# Christmas_Tree_2_1.net
KiCad netlist of a schematic drawn in EAGLE
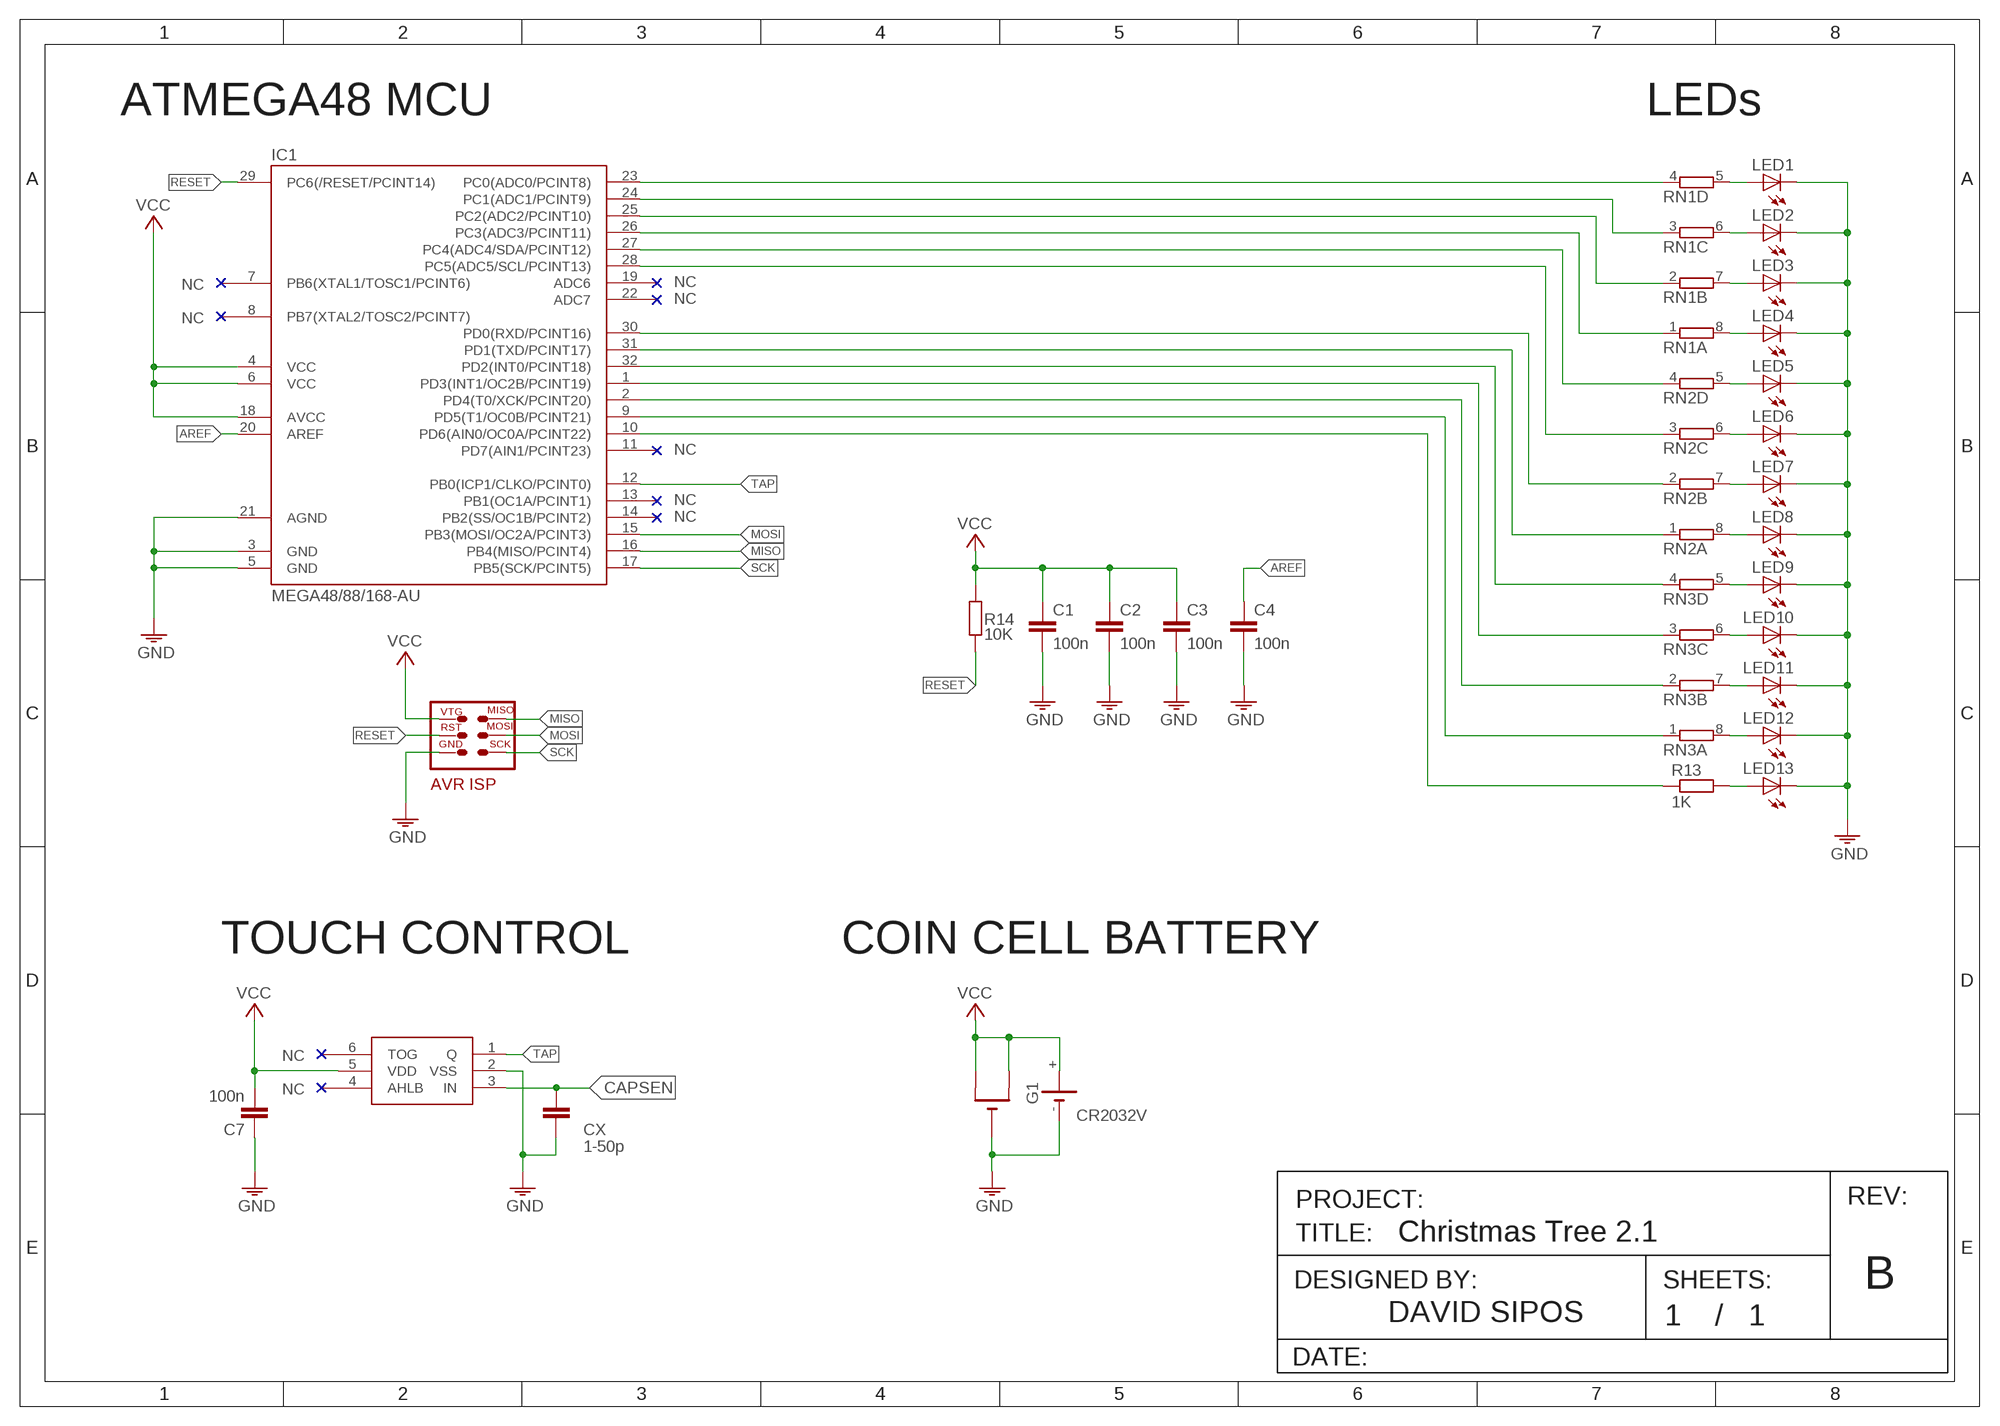
[diagram p0: schematic, sheet 1]

(export (version "E")
  (design (tool "Eeschema 10.0.6"))
  (components
    (comp (ref "BAT")
      (value "CR2032SMT")
      (footprint "eagle-import:CR2032-SMD")
      (libsource (lib "eagle-import") (part "CR2032SMT"))
    )
    (comp (ref "C1")
      (value "100n")
      (footprint "eagle-import:C0402K")
      (libsource (lib "eagle-import") (part "C-EUC0402K"))
    )
    (comp (ref "C2")
      (value "100n")
      (footprint "eagle-import:C0402K")
      (libsource (lib "eagle-import") (part "C-EUC0402K"))
    )
    (comp (ref "C3")
      (value "100n")
      (footprint "eagle-import:C0402K")
      (libsource (lib "eagle-import") (part "C-EUC0402K"))
    )
    (comp (ref "C4")
      (value "100n")
      (footprint "eagle-import:C0402K")
      (libsource (lib "eagle-import") (part "C-EUC0402K"))
    )
    (comp (ref "C7")
      (value "100n")
      (footprint "eagle-import:C0402K")
      (libsource (lib "eagle-import") (part "C-EUC0402K"))
    )
    (comp (ref "CX")
      (value "1-50p")
      (footprint "eagle-import:C0402K")
      (libsource (lib "eagle-import") (part "C-EUC0402K"))
    )
    (comp (ref "G1")
      (value "CR2032V")
      (footprint "eagle-import:CR2032V")
      (libsource (lib "eagle-import") (part "CR2032V"))
    )
    (comp (ref "IC1")
      (value "MEGA48/88/168-AU")
      (footprint "eagle-import:TQFP32-08")
      (libsource (lib "eagle-import") (part "MEGA48/88/168-AU"))
    )
    (comp (ref "LED1")
      (value "LEDCHIPLED_0805")
      (footprint "eagle-import:CHIPLED_0805")
      (libsource (lib "eagle-import") (part "LEDCHIPLED_0805"))
    )
    (comp (ref "LED2")
      (value "LEDCHIPLED_0805")
      (footprint "eagle-import:CHIPLED_0805")
      (libsource (lib "eagle-import") (part "LEDCHIPLED_0805"))
    )
    (comp (ref "LED3")
      (value "LEDCHIPLED_0805")
      (footprint "eagle-import:CHIPLED_0805")
      (libsource (lib "eagle-import") (part "LEDCHIPLED_0805"))
    )
    (comp (ref "LED4")
      (value "LEDCHIPLED_0805")
      (footprint "eagle-import:CHIPLED_0805")
      (libsource (lib "eagle-import") (part "LEDCHIPLED_0805"))
    )
    (comp (ref "LED5")
      (value "LEDCHIPLED_0805")
      (footprint "eagle-import:CHIPLED_0805")
      (libsource (lib "eagle-import") (part "LEDCHIPLED_0805"))
    )
    (comp (ref "LED6")
      (value "LEDCHIPLED_0805")
      (footprint "eagle-import:CHIPLED_0805")
      (libsource (lib "eagle-import") (part "LEDCHIPLED_0805"))
    )
    (comp (ref "LED7")
      (value "LEDCHIPLED_0805")
      (footprint "eagle-import:CHIPLED_0805")
      (libsource (lib "eagle-import") (part "LEDCHIPLED_0805"))
    )
    (comp (ref "LED8")
      (value "LEDCHIPLED_0805")
      (footprint "eagle-import:CHIPLED_0805")
      (libsource (lib "eagle-import") (part "LEDCHIPLED_0805"))
    )
    (comp (ref "LED9")
      (value "LEDCHIPLED_0805")
      (footprint "eagle-import:CHIPLED_0805")
      (libsource (lib "eagle-import") (part "LEDCHIPLED_0805"))
    )
    (comp (ref "LED10")
      (value "LEDCHIPLED_0805")
      (footprint "eagle-import:CHIPLED_0805")
      (libsource (lib "eagle-import") (part "LEDCHIPLED_0805"))
    )
    (comp (ref "LED11")
      (value "LEDCHIPLED_0805")
      (footprint "eagle-import:CHIPLED_0805")
      (libsource (lib "eagle-import") (part "LEDCHIPLED_0805"))
    )
    (comp (ref "LED12")
      (value "LEDCHIPLED_0805")
      (footprint "eagle-import:CHIPLED_0805")
      (libsource (lib "eagle-import") (part "LEDCHIPLED_0805"))
    )
    (comp (ref "LED13")
      (value "LEDCHIPLED_0805")
      (footprint "eagle-import:CHIPLED_0805")
      (libsource (lib "eagle-import") (part "LEDCHIPLED_0805"))
    )
    (comp (ref "R13")
      (value "1K")
      (footprint "eagle-import:R0402")
      (libsource (lib "eagle-import") (part "R-EU_R0402"))
    )
    (comp (ref "R14")
      (value "10K")
      (footprint "eagle-import:R0402")
      (libsource (lib "eagle-import") (part "R-EU_R0402"))
    )
    (comp (ref "RN1")
      (value "4R-N0603-ARC")
      (footprint "eagle-import:0603-ARC")
      (libsource (lib "eagle-import") (part "4R-N0603-ARC"))
    )
    (comp (ref "RN2")
      (value "4R-N0603-ARC")
      (footprint "eagle-import:0603-ARC")
      (libsource (lib "eagle-import") (part "4R-N0603-ARC"))
    )
    (comp (ref "RN3")
      (value "4R-N0603-ARC")
      (footprint "eagle-import:0603-ARC")
      (libsource (lib "eagle-import") (part "4R-N0603-ARC"))
    )
    (comp (ref "TTP223E1")
      (value "TTP223E")
      (footprint "eagle-import:SOT23-6")
      (libsource (lib "eagle-import") (part "TTP223E"))
    )
    (comp (ref "U$12")
      (value "ISP")
      (footprint "eagle-import:ISP")
      (libsource (lib "eagle-import") (part "ISP"))
    )
  )
  (nets
    (net (code "1") (name "AREF") (class "Default")
      (node (ref "C4") (pin "1") (pinfunction "1_1") (pintype "passive"))
      (node (ref "IC1") (pin "20") (pinfunction "AREF_20") (pintype "passive"))
    )
    (net (code "2") (name "CAPSEN") (class "Default")
      (node (ref "CX") (pin "2") (pinfunction "2_2") (pintype "passive"))
      (node (ref "TTP223E1") (pin "3") (pinfunction "IN_3") (pintype "bidirectional"))
    )
    (net (code "3") (name "GND") (class "Default")
      (node (ref "BAT") (pin "-") (pinfunction "-_-") (pintype "passive"))
      (node (ref "C1") (pin "2") (pinfunction "2_2") (pintype "passive"))
      (node (ref "C2") (pin "2") (pinfunction "2_2") (pintype "passive"))
      (node (ref "C3") (pin "2") (pinfunction "2_2") (pintype "passive"))
      (node (ref "C4") (pin "2") (pinfunction "2_2") (pintype "passive"))
      (node (ref "C7") (pin "1") (pinfunction "1_1") (pintype "passive"))
      (node (ref "CX") (pin "1") (pinfunction "1_1") (pintype "passive"))
      (node (ref "G1") (pin "-") (pinfunction "-_-") (pintype "passive"))
      (node (ref "IC1") (pin "21") (pinfunction "AGND_21") (pintype "power_in"))
      (node (ref "IC1") (pin "3") (pinfunction "GND_3") (pintype "power_in"))
      (node (ref "IC1") (pin "5") (pinfunction "GND_5") (pintype "power_in"))
      (node (ref "LED1") (pin "C") (pinfunction "C_C") (pintype "passive"))
      (node (ref "LED10") (pin "C") (pinfunction "C_C") (pintype "passive"))
      (node (ref "LED11") (pin "C") (pinfunction "C_C") (pintype "passive"))
      (node (ref "LED12") (pin "C") (pinfunction "C_C") (pintype "passive"))
      (node (ref "LED13") (pin "C") (pinfunction "C_C") (pintype "passive"))
      (node (ref "LED2") (pin "C") (pinfunction "C_C") (pintype "passive"))
      (node (ref "LED3") (pin "C") (pinfunction "C_C") (pintype "passive"))
      (node (ref "LED4") (pin "C") (pinfunction "C_C") (pintype "passive"))
      (node (ref "LED5") (pin "C") (pinfunction "C_C") (pintype "passive"))
      (node (ref "LED6") (pin "C") (pinfunction "C_C") (pintype "passive"))
      (node (ref "LED7") (pin "C") (pinfunction "C_C") (pintype "passive"))
      (node (ref "LED8") (pin "C") (pinfunction "C_C") (pintype "passive"))
      (node (ref "LED9") (pin "C") (pinfunction "C_C") (pintype "passive"))
      (node (ref "TTP223E1") (pin "2") (pinfunction "VSS_2") (pintype "bidirectional"))
      (node (ref "U$12") (pin "6") (pinfunction "6_6") (pintype "passive"))
    )
    (net (code "4") (name "MISO") (class "Default")
      (node (ref "IC1") (pin "16") (pinfunction "PB4(MISO/PCINT4)_16") (pintype "bidirectional"))
      (node (ref "U$12") (pin "1") (pinfunction "1_1") (pintype "passive"))
    )
    (net (code "5") (name "MOSI") (class "Default")
      (node (ref "IC1") (pin "15") (pinfunction "PB3(MOSI/OC2A/PCINT3)_15") (pintype "bidirectional"))
      (node (ref "U$12") (pin "4") (pinfunction "4_4") (pintype "passive"))
    )
    (net (code "6") (name "Net-(IC1-PC0(ADC0{slash}PCINT8))") (class "Default")
      (node (ref "IC1") (pin "23") (pinfunction "PC0(ADC0/PCINT8)_23") (pintype "bidirectional"))
      (node (ref "RN1") (pin "4") (pinfunction "1_4") (pintype "passive"))
    )
    (net (code "7") (name "Net-(IC1-PC1(ADC1{slash}PCINT9))") (class "Default")
      (node (ref "IC1") (pin "24") (pinfunction "PC1(ADC1/PCINT9)_24") (pintype "bidirectional"))
      (node (ref "RN1") (pin "3") (pinfunction "1_3") (pintype "passive"))
    )
    (net (code "8") (name "Net-(IC1-PC2(ADC2{slash}PCINT10))") (class "Default")
      (node (ref "IC1") (pin "25") (pinfunction "PC2(ADC2/PCINT10)_25") (pintype "bidirectional"))
      (node (ref "RN1") (pin "2") (pinfunction "1_2") (pintype "passive"))
    )
    (net (code "9") (name "Net-(IC1-PC3(ADC3{slash}PCINT11))") (class "Default")
      (node (ref "IC1") (pin "26") (pinfunction "PC3(ADC3/PCINT11)_26") (pintype "bidirectional"))
      (node (ref "RN1") (pin "1") (pinfunction "1_1") (pintype "passive"))
    )
    (net (code "10") (name "Net-(IC1-PC4(ADC4{slash}SDA{slash}PCINT12))") (class "Default")
      (node (ref "IC1") (pin "27") (pinfunction "PC4(ADC4/SDA/PCINT12)_27") (pintype "bidirectional"))
      (node (ref "RN2") (pin "4") (pinfunction "1_4") (pintype "passive"))
    )
    (net (code "11") (name "Net-(IC1-PC5(ADC5{slash}SCL{slash}PCINT13))") (class "Default")
      (node (ref "IC1") (pin "28") (pinfunction "PC5(ADC5/SCL/PCINT13)_28") (pintype "bidirectional"))
      (node (ref "RN2") (pin "3") (pinfunction "1_3") (pintype "passive"))
    )
    (net (code "12") (name "Net-(IC1-PD0(RXD{slash}PCINT16))") (class "Default")
      (node (ref "IC1") (pin "30") (pinfunction "PD0(RXD/PCINT16)_30") (pintype "bidirectional"))
      (node (ref "RN2") (pin "2") (pinfunction "1_2") (pintype "passive"))
    )
    (net (code "13") (name "Net-(IC1-PD1(TXD{slash}PCINT17))") (class "Default")
      (node (ref "IC1") (pin "31") (pinfunction "PD1(TXD/PCINT17)_31") (pintype "bidirectional"))
      (node (ref "RN2") (pin "1") (pinfunction "1_1") (pintype "passive"))
    )
    (net (code "14") (name "Net-(IC1-PD2(INT0{slash}PCINT18))") (class "Default")
      (node (ref "IC1") (pin "32") (pinfunction "PD2(INT0/PCINT18)_32") (pintype "bidirectional"))
      (node (ref "RN3") (pin "4") (pinfunction "1_4") (pintype "passive"))
    )
    (net (code "15") (name "Net-(IC1-PD3(INT1{slash}OC2B{slash}PCINT19))") (class "Default")
      (node (ref "IC1") (pin "1") (pinfunction "PD3(INT1/OC2B/PCINT19)_1") (pintype "bidirectional"))
      (node (ref "RN3") (pin "3") (pinfunction "1_3") (pintype "passive"))
    )
    (net (code "16") (name "Net-(IC1-PD4(T0{slash}XCK{slash}PCINT20))") (class "Default")
      (node (ref "IC1") (pin "2") (pinfunction "PD4(T0/XCK/PCINT20)_2") (pintype "bidirectional"))
      (node (ref "RN3") (pin "2") (pinfunction "1_2") (pintype "passive"))
    )
    (net (code "17") (name "Net-(IC1-PD5(T1{slash}OC0B{slash}PCINT21))") (class "Default")
      (node (ref "IC1") (pin "9") (pinfunction "PD5(T1/OC0B/PCINT21)_9") (pintype "bidirectional"))
      (node (ref "RN3") (pin "1") (pinfunction "1_1") (pintype "passive"))
    )
    (net (code "18") (name "Net-(IC1-PD6(AIN0{slash}OC0A{slash}PCINT22))") (class "Default")
      (node (ref "IC1") (pin "10") (pinfunction "PD6(AIN0/OC0A/PCINT22)_10") (pintype "bidirectional"))
      (node (ref "R13") (pin "1") (pinfunction "1_1") (pintype "passive"))
    )
    (net (code "19") (name "Net-(LED13-PadA)") (class "Default")
      (node (ref "LED13") (pin "A") (pinfunction "A_A") (pintype "passive"))
      (node (ref "R13") (pin "2") (pinfunction "2_2") (pintype "passive"))
    )
    (net (code "20") (name "Net-(RN1A-2)") (class "Default")
      (node (ref "LED4") (pin "A") (pinfunction "A_A") (pintype "passive"))
      (node (ref "RN1") (pin "8") (pinfunction "2_8") (pintype "passive"))
    )
    (net (code "21") (name "Net-(RN1B-2)") (class "Default")
      (node (ref "LED3") (pin "A") (pinfunction "A_A") (pintype "passive"))
      (node (ref "RN1") (pin "7") (pinfunction "2_7") (pintype "passive"))
    )
    (net (code "22") (name "Net-(RN1C-2)") (class "Default")
      (node (ref "LED2") (pin "A") (pinfunction "A_A") (pintype "passive"))
      (node (ref "RN1") (pin "6") (pinfunction "2_6") (pintype "passive"))
    )
    (net (code "23") (name "Net-(RN1D-2)") (class "Default")
      (node (ref "LED1") (pin "A") (pinfunction "A_A") (pintype "passive"))
      (node (ref "RN1") (pin "5") (pinfunction "2_5") (pintype "passive"))
    )
    (net (code "24") (name "Net-(RN2A-2)") (class "Default")
      (node (ref "LED8") (pin "A") (pinfunction "A_A") (pintype "passive"))
      (node (ref "RN2") (pin "8") (pinfunction "2_8") (pintype "passive"))
    )
    (net (code "25") (name "Net-(RN2B-2)") (class "Default")
      (node (ref "LED7") (pin "A") (pinfunction "A_A") (pintype "passive"))
      (node (ref "RN2") (pin "7") (pinfunction "2_7") (pintype "passive"))
    )
    (net (code "26") (name "Net-(RN2C-2)") (class "Default")
      (node (ref "LED6") (pin "A") (pinfunction "A_A") (pintype "passive"))
      (node (ref "RN2") (pin "6") (pinfunction "2_6") (pintype "passive"))
    )
    (net (code "27") (name "Net-(RN2D-2)") (class "Default")
      (node (ref "LED5") (pin "A") (pinfunction "A_A") (pintype "passive"))
      (node (ref "RN2") (pin "5") (pinfunction "2_5") (pintype "passive"))
    )
    (net (code "28") (name "Net-(RN3A-2)") (class "Default")
      (node (ref "LED12") (pin "A") (pinfunction "A_A") (pintype "passive"))
      (node (ref "RN3") (pin "8") (pinfunction "2_8") (pintype "passive"))
    )
    (net (code "29") (name "Net-(RN3B-2)") (class "Default")
      (node (ref "LED11") (pin "A") (pinfunction "A_A") (pintype "passive"))
      (node (ref "RN3") (pin "7") (pinfunction "2_7") (pintype "passive"))
    )
    (net (code "30") (name "Net-(RN3C-2)") (class "Default")
      (node (ref "LED10") (pin "A") (pinfunction "A_A") (pintype "passive"))
      (node (ref "RN3") (pin "6") (pinfunction "2_6") (pintype "passive"))
    )
    (net (code "31") (name "Net-(RN3D-2)") (class "Default")
      (node (ref "LED9") (pin "A") (pinfunction "A_A") (pintype "passive"))
      (node (ref "RN3") (pin "5") (pinfunction "2_5") (pintype "passive"))
    )
    (net (code "32") (name "RESET") (class "Default")
      (node (ref "IC1") (pin "29") (pinfunction "PC6(/RESET/PCINT14)_29") (pintype "bidirectional"))
      (node (ref "R14") (pin "1") (pinfunction "1_1") (pintype "passive"))
      (node (ref "U$12") (pin "5") (pinfunction "5_5") (pintype "passive"))
    )
    (net (code "33") (name "SCK") (class "Default")
      (node (ref "IC1") (pin "17") (pinfunction "PB5(SCK/PCINT5)_17") (pintype "bidirectional"))
      (node (ref "U$12") (pin "3") (pinfunction "3_3") (pintype "passive"))
    )
    (net (code "34") (name "TAP") (class "Default")
      (node (ref "IC1") (pin "12") (pinfunction "PB0(ICP1/CLKO/PCINT0)_12") (pintype "bidirectional"))
      (node (ref "TTP223E1") (pin "1") (pinfunction "Q_1") (pintype "bidirectional"))
    )
    (net (code "35") (name "VCC") (class "Default")
      (node (ref "BAT") (pin "+$1") (pinfunction "+_+$1") (pintype "passive"))
      (node (ref "BAT") (pin "+$2") (pinfunction "+1_+$2") (pintype "passive"))
      (node (ref "C1") (pin "1") (pinfunction "1_1") (pintype "passive"))
      (node (ref "C2") (pin "1") (pinfunction "1_1") (pintype "passive"))
      (node (ref "C3") (pin "1") (pinfunction "1_1") (pintype "passive"))
      (node (ref "C7") (pin "2") (pinfunction "2_2") (pintype "passive"))
      (node (ref "G1") (pin "+") (pinfunction "+_+") (pintype "passive"))
      (node (ref "G1") (pin "+@1") (pinfunction "+_+@1") (pintype "passive"))
      (node (ref "IC1") (pin "18") (pinfunction "AVCC_18") (pintype "passive"))
      (node (ref "IC1") (pin "4") (pinfunction "VCC_4") (pintype "power_in"))
      (node (ref "IC1") (pin "6") (pinfunction "VCC_6") (pintype "power_in"))
      (node (ref "R14") (pin "2") (pinfunction "2_2") (pintype "passive"))
      (node (ref "TTP223E1") (pin "5") (pinfunction "VDD_5") (pintype "bidirectional"))
      (node (ref "U$12") (pin "2") (pinfunction "2_2") (pintype "passive"))
    )
    (net (code "36") (name "unconnected-(IC1-ADC6-Pad19)") (class "Default")
      (node (ref "IC1") (pin "19") (pinfunction "ADC6_19") (pintype "passive"))
    )
    (net (code "37") (name "unconnected-(IC1-ADC7-Pad22)") (class "Default")
      (node (ref "IC1") (pin "22") (pinfunction "ADC7_22") (pintype "passive"))
    )
    (net (code "38") (name "unconnected-(IC1-PB1(OC1A{slash}PCINT1)-Pad13)") (class "Default")
      (node (ref "IC1") (pin "13") (pinfunction "PB1(OC1A/PCINT1)_13") (pintype "bidirectional"))
    )
    (net (code "39") (name "unconnected-(IC1-PB2(SS{slash}OC1B{slash}PCINT2)-Pad14)") (class "Default")
      (node (ref "IC1") (pin "14") (pinfunction "PB2(SS/OC1B/PCINT2)_14") (pintype "bidirectional"))
    )
    (net (code "40") (name "unconnected-(IC1-PB6(XTAL1{slash}TOSC1{slash}PCINT6)-Pad7)") (class "Default")
      (node (ref "IC1") (pin "7") (pinfunction "PB6(XTAL1/TOSC1/PCINT6)_7") (pintype "bidirectional"))
    )
    (net (code "41") (name "unconnected-(IC1-PB7(XTAL2{slash}TOSC2{slash}PCINT7)-Pad8)") (class "Default")
      (node (ref "IC1") (pin "8") (pinfunction "PB7(XTAL2/TOSC2/PCINT7)_8") (pintype "bidirectional"))
    )
    (net (code "42") (name "unconnected-(IC1-PD7(AIN1{slash}PCINT23)-Pad11)") (class "Default")
      (node (ref "IC1") (pin "11") (pinfunction "PD7(AIN1/PCINT23)_11") (pintype "bidirectional"))
    )
    (net (code "43") (name "unconnected-(TTP223E1-AHLB-Pad4)") (class "Default")
      (node (ref "TTP223E1") (pin "4") (pinfunction "AHLB_4") (pintype "bidirectional"))
    )
    (net (code "44") (name "unconnected-(TTP223E1-TOG-Pad6)") (class "Default")
      (node (ref "TTP223E1") (pin "6") (pinfunction "TOG_6") (pintype "bidirectional"))
    )
  )
)
